# Sheet1.net
KiCad netlist of a schematic drawn in Altium Designer
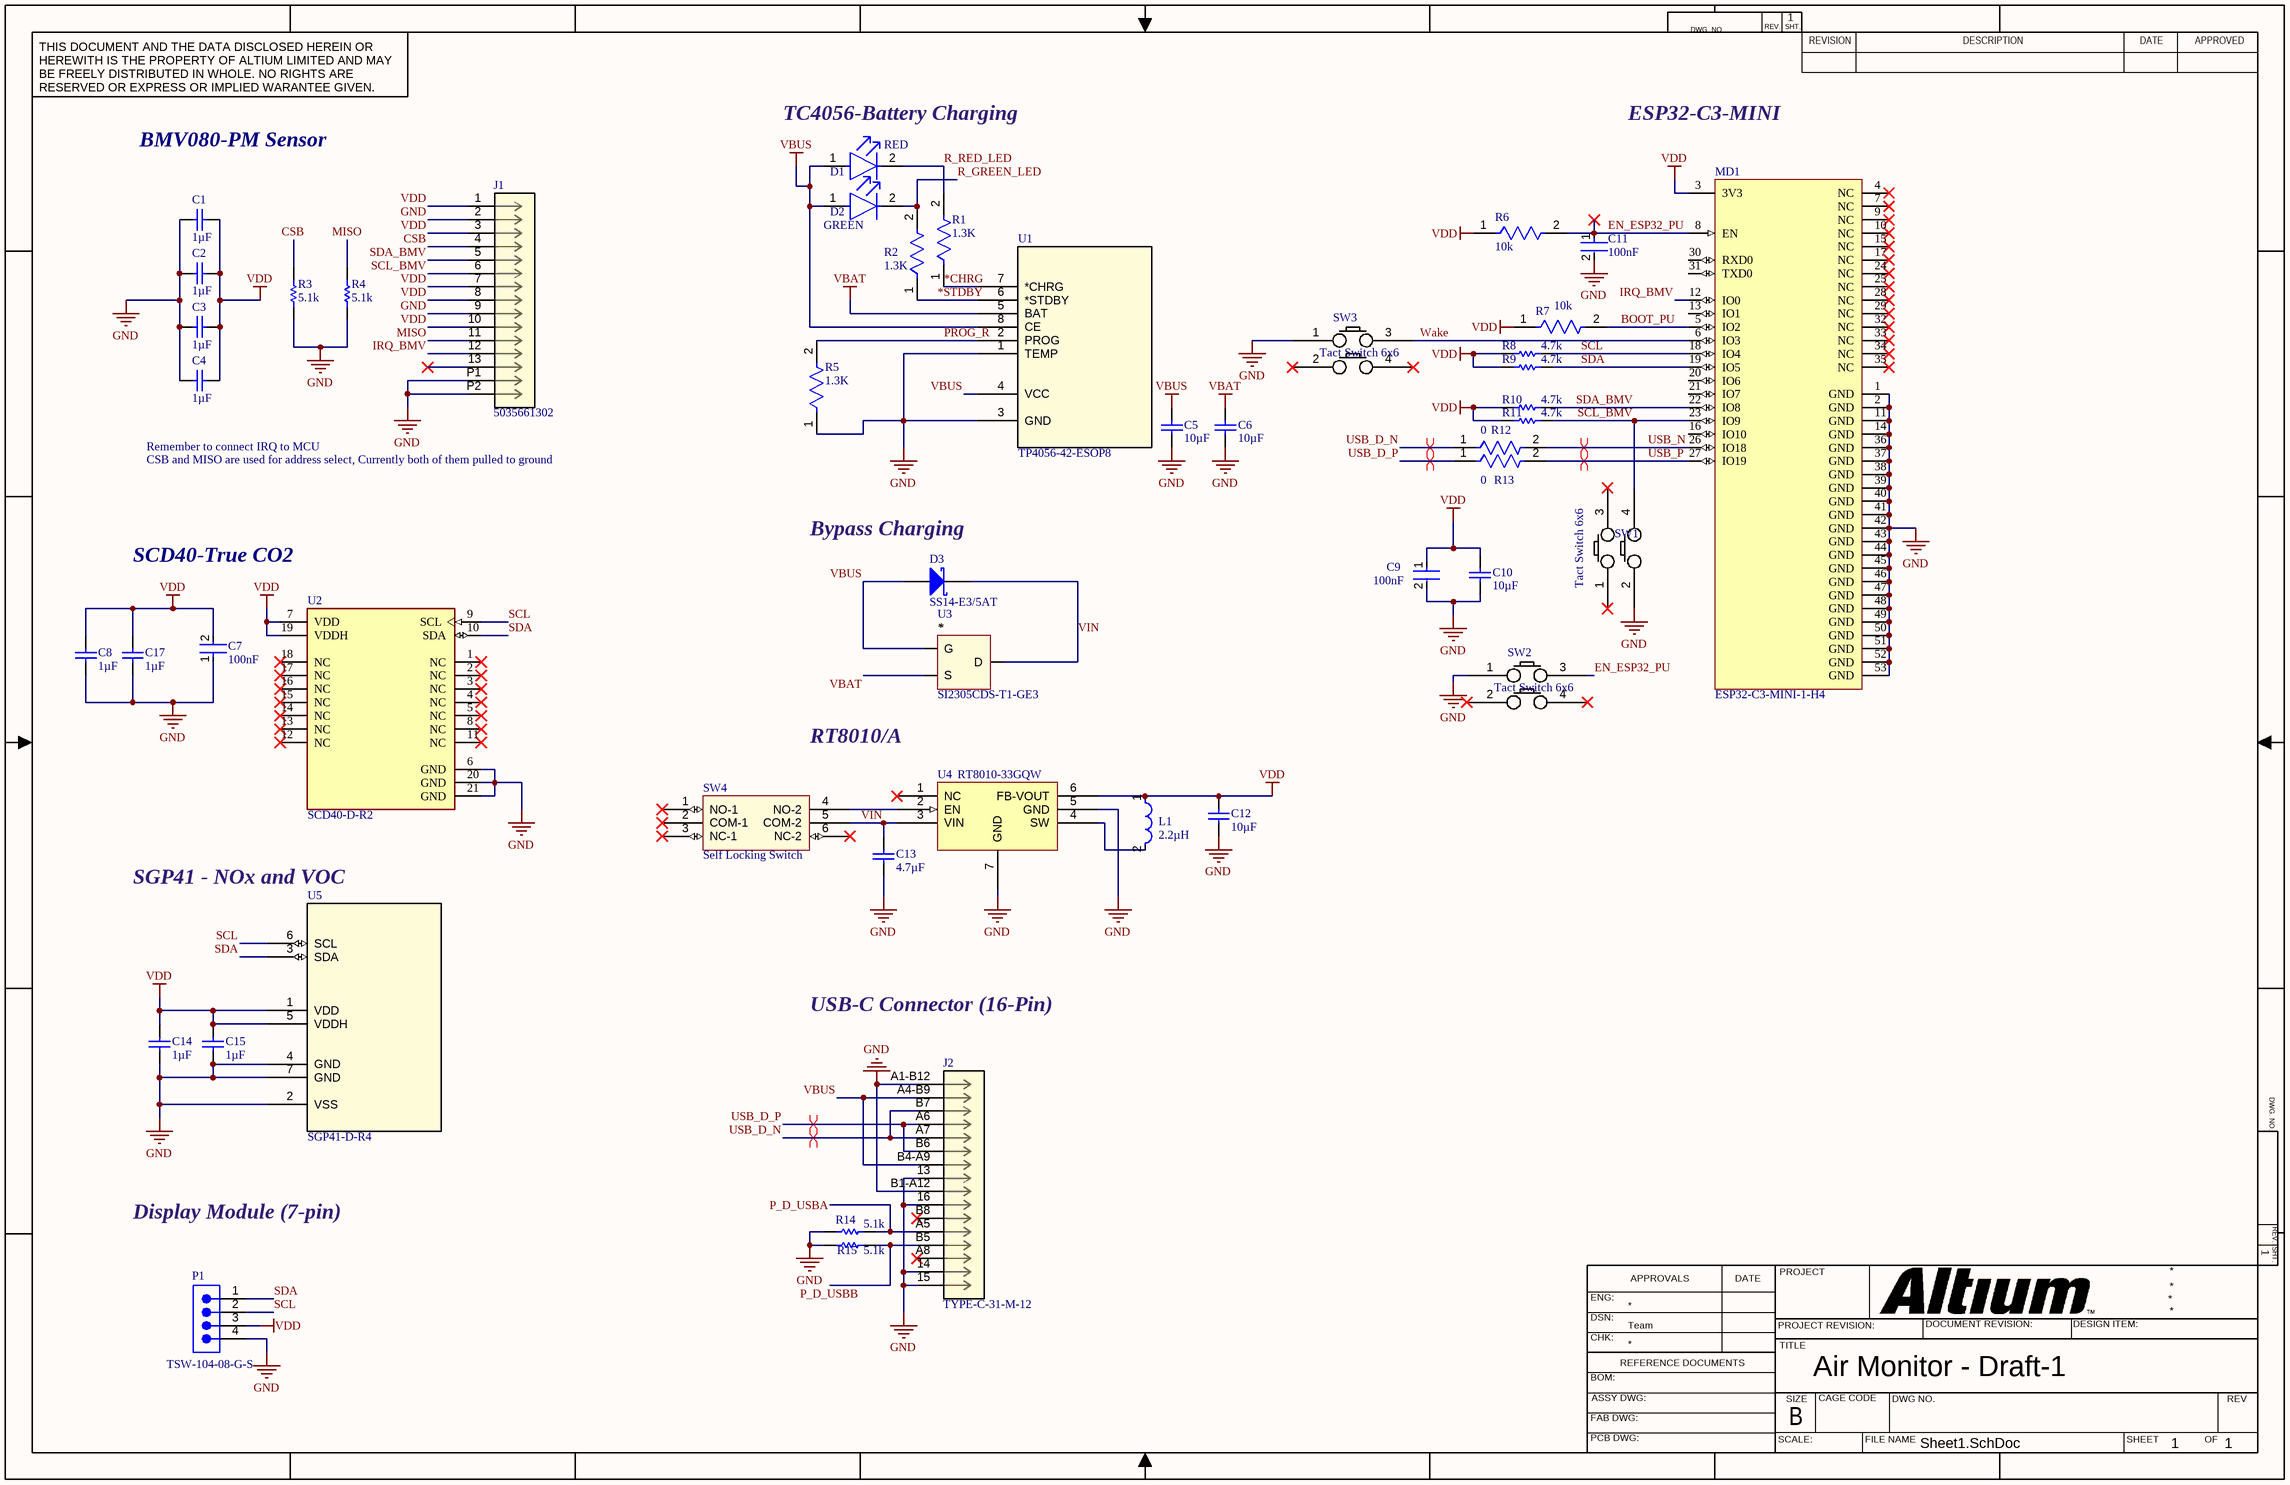
[diagram p0: Sheet1.SchDoc]

(export (version "E")
  (design (tool "Eeschema 10.0.6"))
  (components
    (comp (ref "C1")
      (value "1µF")
      (footprint "CAPC1608X90X35LL15T15")
      (description "16V 1uF X7R ±10% 0603 Multilayer Ceramic Capacitors MLCC - SMD/SMT ROHS")
      (fields (field (name "TOLERANCE") "10%") (field (name "VOLTAGE") "16V"))
      (libsource (lib "Shubhang Kulkarni") (part "CAP"))
    )
    (comp (ref "C2")
      (value "1µF")
      (footprint "CAPC1608X90X35LL15T15")
      (description "16V 1uF X7R ±10% 0603 Multilayer Ceramic Capacitors MLCC - SMD/SMT ROHS")
      (fields (field (name "TOLERANCE") "10%") (field (name "VOLTAGE") "16V"))
      (libsource (lib "Shubhang Kulkarni") (part "CAP"))
    )
    (comp (ref "C3")
      (value "1µF")
      (footprint "CAPC1608X90X35LL15T15")
      (description "16V 1uF X7R ±10% 0603 Multilayer Ceramic Capacitors MLCC - SMD/SMT ROHS")
      (fields (field (name "TOLERANCE") "10%") (field (name "VOLTAGE") "16V"))
      (libsource (lib "Shubhang Kulkarni") (part "CAP"))
    )
    (comp (ref "C4")
      (value "1µF")
      (footprint "CAPC1608X90X35LL15T15")
      (description "16V 1uF X7R ±10% 0603 Multilayer Ceramic Capacitors MLCC - SMD/SMT ROHS")
      (fields (field (name "TOLERANCE") "10%") (field (name "VOLTAGE") "16V"))
      (libsource (lib "Shubhang Kulkarni") (part "CAP"))
    )
    (comp (ref "C5")
      (value "10µF")
      (footprint "CAPC2013X140X45LL15T25")
      (description "Multilayer Ceramic Capacitor, 10 uF, 10 V, ± 10%, X7R, 0805 [2012 Metric]")
      (fields (field (name "TOLERANCE") "10%") (field (name "VOLTAGE") "10V"))
      (libsource (lib "Shubhang Kulkarni") (part "CAP"))
    )
    (comp (ref "C6")
      (value "10µF")
      (footprint "CAPC2013X140X45LL15T25")
      (description "Multilayer Ceramic Capacitor, 10 uF, 10 V, ± 10%, X7R, 0805 [2012 Metric]")
      (fields (field (name "TOLERANCE") "10%") (field (name "VOLTAGE") "10V"))
      (libsource (lib "Shubhang Kulkarni") (part "CAP"))
    )
    (comp (ref "C7")
      (value "100nF")
      (footprint "FP-CC0603-DA-IPC_B")
      (description "Multilayer Ceramic Capacitor, CC Series, 0.1 - F, - 10%, X7R, 50 V, 0603 [1608 Metric]")
      (fields (field (name "VOLTAGE") "50V") (field (name "TOLERANCE") "10%"))
      (libsource (lib "Shubhang Kulkarni") (part "11868f565c42a9108669ba33697ecf6"))
    )
    (comp (ref "C8")
      (value "1µF")
      (footprint "CAPC1608X90X35LL15T15")
      (description "16V 1uF X7R ±10% 0603 Multilayer Ceramic Capacitors MLCC - SMD/SMT ROHS")
      (fields (field (name "TOLERANCE") "10%") (field (name "VOLTAGE") "16V"))
      (libsource (lib "Shubhang Kulkarni") (part "CAP"))
    )
    (comp (ref "C9")
      (value "100nF")
      (footprint "FP-CC0603-DA-IPC_B")
      (description "Multilayer Ceramic Capacitor, CC Series, 0.1 - F, - 10%, X7R, 50 V, 0603 [1608 Metric]")
      (fields (field (name "VOLTAGE") "50V") (field (name "TOLERANCE") "10%"))
      (libsource (lib "Shubhang Kulkarni") (part "11868f565c42a9108669ba33697ecf6"))
    )
    (comp (ref "C10")
      (value "10µF")
      (footprint "CAPC2013X140X45LL15T25")
      (description "Multilayer Ceramic Capacitor, 10 uF, 10 V, ± 10%, X7R, 0805 [2012 Metric]")
      (fields (field (name "TOLERANCE") "10%") (field (name "VOLTAGE") "10V"))
      (libsource (lib "Shubhang Kulkarni") (part "CAP"))
    )
    (comp (ref "C11")
      (value "100nF")
      (footprint "FP-CC0603-DA-IPC_B")
      (description "Multilayer Ceramic Capacitor, CC Series, 0.1 - F, - 10%, X7R, 50 V, 0603 [1608 Metric]")
      (fields (field (name "VOLTAGE") "50V") (field (name "TOLERANCE") "10%"))
      (libsource (lib "Shubhang Kulkarni") (part "11868f565c42a9108669ba33697ecf6"))
    )
    (comp (ref "C12")
      (value "10µF")
      (footprint "CAPC2013X140X45LL15T25")
      (description "Multilayer Ceramic Capacitor, 10 uF, 10 V, ± 10%, X7R, 0805 [2012 Metric]")
      (fields (field (name "TOLERANCE") "10%") (field (name "VOLTAGE") "10V"))
      (libsource (lib "Shubhang Kulkarni") (part "CAP"))
    )
    (comp (ref "C13")
      (value "4.7µF")
      (footprint "CAPC2013X140X50LL20T25")
      (description "0805 Standard 4.7UF Ceramic Multilayer Cap, 25V DC, +85C, X5R Dielectric, +/-10% SMD")
      (fields (field (name "VOLTAGE") "25V") (field (name "TOLERANCE") "10%"))
      (libsource (lib "Shubhang Kulkarni") (part "CAP"))
    )
    (comp (ref "C14")
      (value "1µF")
      (footprint "CAPC1608X90X35LL15T15")
      (description "16V 1uF X7R ±10% 0603 Multilayer Ceramic Capacitors MLCC - SMD/SMT ROHS")
      (fields (field (name "TOLERANCE") "10%") (field (name "VOLTAGE") "16V"))
      (libsource (lib "Shubhang Kulkarni") (part "CAP"))
    )
    (comp (ref "C15")
      (value "1µF")
      (footprint "CAPC1608X90X35LL15T15")
      (description "16V 1uF X7R ±10% 0603 Multilayer Ceramic Capacitors MLCC - SMD/SMT ROHS")
      (fields (field (name "TOLERANCE") "10%") (field (name "VOLTAGE") "16V"))
      (libsource (lib "Shubhang Kulkarni") (part "CAP"))
    )
    (comp (ref "C17")
      (value "1µF")
      (footprint "CAPC1608X90X35LL15T15")
      (description "16V 1uF X7R ±10% 0603 Multilayer Ceramic Capacitors MLCC - SMD/SMT ROHS")
      (fields (field (name "TOLERANCE") "10%") (field (name "VOLTAGE") "16V"))
      (libsource (lib "Shubhang Kulkarni") (part "CAP"))
    )
    (comp (ref "D1")
      (value "RED")
      (footprint "FP-SM0805YCL-MFG")
      (description "LED YELLOW CLEAR 0805 SMD")
      (libsource (lib "Altium Content Vault") (part "ab1c01a81903e929fc6c44469aada92"))
    )
    (comp (ref "D2")
      (value "GREEN")
      (footprint "FP-SM0805YCL-MFG")
      (description "LED YELLOW CLEAR 0805 SMD")
      (libsource (lib "Altium Content Vault") (part "ab1c01a81903e929fc6c44469aada92"))
    )
    (comp (ref "D3")
      (value "SS14-E3/5AT")
      (footprint "VISH-DO-214AC-2_V")
      (description "Rectifier Diode, Schottky, 1 Phase, 1 Element, 1A, 40V V(RRM), Silicon, DO-214AC")
      (libsource (lib "Shubhang Kulkarni") (part "VISH-DSKY_A1K2-2"))
    )
    (comp (ref "J1")
      (value "5035661302")
      (footprint "CON_5035661302_MOL")
      (fields (field (name "COPYRIGHT") "Copyright (C) 2026 Ultra Librarian. All rights reserved."))
      (libsource (lib "Shubhang Kulkarni") (part "5035661302"))
    )
    (comp (ref "J2")
      (value "TYPE-C-31-M-12")
      (footprint "CONN12_C-31-M-12_HRO")
      (description "Description")
      (fields (field (name "COPYRIGHT") "Copyright (C) 2025 Ultra Librarian. All rights reserved."))
      (libsource (lib "Shubhang Kulkarni") (part "TYPE-C-31-M-12"))
    )
    (comp (ref "L1")
      (value "2.2µH")
      (footprint "FP-NR6028-MFG")
      (description "Inductor Power Shielded Wirewound 2.2uH 30% 100KHz Ferrite 3.7A 0.026Ohm DCR 2424 T/R")
      (fields (field (name "TOLERANCE") "30%") (field (name "Comment") "NRS6028T2R2NMGJ"))
      (libsource (lib "Shubhang Kulkarni") (part "725321dda6339637d4d059423bc1c3c"))
    )
    (comp (ref "MD1")
      (value "ESP32-C3-MINI-1-H4")
      (footprint "FP-ESP32-C3-MINI-1-H4-MFG")
      (description "-96dBm 20.5dBm PCBAntenna 2.4GHz SMD, 13.2x16.6mm WiFi Modules ROHS")
      (libsource (lib "Shubhang Kulkarni") (part "ESP32-C3-MINI-1-H4"))
    )
    (comp (ref "P1")
      (value "TSW-104-08-G-S")
      (footprint "SMTC-TSW-104-08-X-S")
      (description "0.025\" SQ Post Header, Through-hole, Vertical, -55 to 125 degC, 2.54 mm Pitch, 4-Pin, Male, RoHS")
      (fields (field (name "MANUFACTURER") "Samtec"))
      (libsource (lib "Altium Content Vault") (part "SMTC-TSW-104-08-X-S"))
    )
    (comp (ref "R1")
      (value "1.3K")
      (footprint "FP-AC0603-IPC_B")
      (description "RES 1.3KΩ 1.00% 0.1W 0603")
      (fields (field (name "TOLERANCE") "1%"))
      (libsource (lib "Altium Content Vault") (part "1029c3af85768c4190bb7ad29bc67b5"))
    )
    (comp (ref "R2")
      (value "1.3K")
      (footprint "FP-AC0603-IPC_B")
      (description "RES 1.3KΩ 1.00% 0.1W 0603")
      (fields (field (name "TOLERANCE") "1%"))
      (libsource (lib "Altium Content Vault") (part "1029c3af85768c4190bb7ad29bc67b5"))
    )
    (comp (ref "R3")
      (value "5.1k")
      (footprint "RESC1608X55X25ML10T15")
      (description "Res Thick Film 0603 5.1K Ohm 1% 0.1W(1/10W) ±100ppm/C Pad SMD T/R")
      (fields (field (name "TOLERANCE") "1%") (field (name "Comment") "RC0603FR-075K1L"))
      (libsource (lib "Shubhang Kulkarni") (part "RES"))
    )
    (comp (ref "R4")
      (value "5.1k")
      (footprint "RESC1608X55X25ML10T15")
      (description "Res Thick Film 0603 5.1K Ohm 1% 0.1W(1/10W) ±100ppm/C Pad SMD T/R")
      (fields (field (name "TOLERANCE") "1%") (field (name "Comment") "RC0603FR-075K1L"))
      (libsource (lib "Shubhang Kulkarni") (part "RES"))
    )
    (comp (ref "R5")
      (value "1.3K")
      (footprint "FP-AC0603-IPC_B")
      (description "RES 1.3KΩ 1.00% 0.1W 0603")
      (fields (field (name "TOLERANCE") "1%"))
      (libsource (lib "Altium Content Vault") (part "1029c3af85768c4190bb7ad29bc67b5"))
    )
    (comp (ref "R6")
      (value "10k")
      (footprint "FP-RC0603-0_55-IPC_C")
      (description "100mW Thick Film Resistors ±100ppm/℃ ±1% 10kΩ 0603 Chip Resistor - Surface Mount ROHS")
      (fields (field (name "TOLERANCE") "1%") (field (name "Comment") "RC0603FR-0710KL"))
      (libsource (lib "Shubhang Kulkarni") (part "1029c3af85768c4190bb7ad29bc67b5"))
    )
    (comp (ref "R7")
      (value "10k")
      (footprint "FP-RC0603-0_55-IPC_C")
      (description "100mW Thick Film Resistors ±100ppm/℃ ±1% 10kΩ 0603 Chip Resistor - Surface Mount ROHS")
      (fields (field (name "TOLERANCE") "1%") (field (name "Comment") "RC0603FR-0710KL"))
      (libsource (lib "Shubhang Kulkarni") (part "1029c3af85768c4190bb7ad29bc67b5"))
    )
    (comp (ref "R8")
      (value "4.7k")
      (footprint "RESC1608X55X25LL10T15")
      (description "Res Thick Film 1.6 x 0.8 mm 4.7K Ohm 1% 0.1W(1/10W) 100ppm/ C Molded SMD Paper T/R")
      (fields (field (name "TOLERANCE") "1%") (field (name "Comment") "RC0603FR-074K7L"))
      (libsource (lib "Shubhang Kulkarni") (part "RES-2"))
    )
    (comp (ref "R9")
      (value "4.7k")
      (footprint "RESC1608X55X25LL10T15")
      (description "Res Thick Film 1.6 x 0.8 mm 4.7K Ohm 1% 0.1W(1/10W) 100ppm/ C Molded SMD Paper T/R")
      (fields (field (name "TOLERANCE") "1%") (field (name "Comment") "RC0603FR-074K7L"))
      (libsource (lib "Shubhang Kulkarni") (part "RES-2"))
    )
    (comp (ref "R10")
      (value "4.7k")
      (footprint "RESC1608X55X25LL10T15")
      (description "Res Thick Film 1.6 x 0.8 mm 4.7K Ohm 1% 0.1W(1/10W) 100ppm/ C Molded SMD Paper T/R")
      (fields (field (name "TOLERANCE") "1%") (field (name "Comment") "RC0603FR-074K7L"))
      (libsource (lib "Shubhang Kulkarni") (part "RES-2"))
    )
    (comp (ref "R11")
      (value "4.7k")
      (footprint "RESC1608X55X25LL10T15")
      (description "Res Thick Film 1.6 x 0.8 mm 4.7K Ohm 1% 0.1W(1/10W) 100ppm/ C Molded SMD Paper T/R")
      (fields (field (name "TOLERANCE") "1%") (field (name "Comment") "RC0603FR-074K7L"))
      (libsource (lib "Shubhang Kulkarni") (part "RES-2"))
    )
    (comp (ref "R12")
      (value "0")
      (footprint "FP-RC0603-MFG")
      (description "Zero Ohm Resistor, Jumper, 0603 [1608 Metric], Thick Film, 100 mW, 1 A, Surface Mount")
      (fields (field (name "TOLERANCE") "1%") (field (name "Comment") "RC0603FR-070RL"))
      (libsource (lib "Shubhang Kulkarni") (part "1029c3af85768c4190bb7ad29bc67b5"))
    )
    (comp (ref "R13")
      (value "0")
      (footprint "FP-RC0603-MFG")
      (description "Zero Ohm Resistor, Jumper, 0603 [1608 Metric], Thick Film, 100 mW, 1 A, Surface Mount")
      (fields (field (name "TOLERANCE") "1%") (field (name "Comment") "RC0603FR-070RL"))
      (libsource (lib "Shubhang Kulkarni") (part "1029c3af85768c4190bb7ad29bc67b5"))
    )
    (comp (ref "R14")
      (value "5.1k")
      (footprint "RESC1608X55X25ML10T15")
      (description "Res Thick Film 0603 5.1K Ohm 1% 0.1W(1/10W) ±100ppm/C Pad SMD T/R")
      (fields (field (name "TOLERANCE") "1%") (field (name "Comment") "RC0603FR-075K1L"))
      (libsource (lib "Shubhang Kulkarni") (part "RES"))
    )
    (comp (ref "R15")
      (value "5.1k")
      (footprint "RESC1608X55X25ML10T15")
      (description "Res Thick Film 0603 5.1K Ohm 1% 0.1W(1/10W) ±100ppm/C Pad SMD T/R")
      (fields (field (name "TOLERANCE") "1%") (field (name "Comment") "RC0603FR-075K1L"))
      (libsource (lib "Shubhang Kulkarni") (part "RES"))
    )
    (comp (ref "SW1")
      (value "Tact Switch 6x6")
      (footprint "Tact Switch 6x6-Footprint-1")
      (description "Tact switch- 6x6mm")
      (libsource (lib "Shubhang Kulkarni") (part "Tact Switch"))
    )
    (comp (ref "SW2")
      (value "Tact Switch 6x6")
      (footprint "Tact Switch 6x6-Footprint-1")
      (description "Tact switch- 6x6mm")
      (libsource (lib "Shubhang Kulkarni") (part "Tact Switch"))
    )
    (comp (ref "SW3")
      (value "Tact Switch 6x6")
      (footprint "Tact Switch 6x6-Footprint-1")
      (description "Tact switch- 6x6mm")
      (libsource (lib "Shubhang Kulkarni") (part "Tact Switch"))
    )
    (comp (ref "SW4")
      (value "Self Locking Switch")
      (footprint "Self Locking Switch-Footprint-1")
      (description "A self locking-latch like switch.")
      (libsource (lib "Shubhang Kulkarni") (part "KFC-5.8C"))
    )
    (comp (ref "U1")
      (value "TP4056-42-ESOP8")
      (footprint "TP4056-42-ESOP8_TPW")
      (description "Description")
      (fields (field (name "COPYRIGHT") "Copyright (C) 2026 Ultra Librarian. All rights reserved."))
      (libsource (lib "Shubhang Kulkarni") (part "TP4056-42-ESOP8"))
    )
    (comp (ref "U2")
      (value "SCD40-D-R2")
      (footprint "FP-SCD40-D-R2-MFG")
      (description "Air Quality Sensor CO2 Sensor 2.5V/3.3V/5V 20-Pin SMD EP T/R")
      (libsource (lib "Shubhang Kulkarni") (part "860b1291be8b6ca23305e01f328347a"))
    )
    (comp (ref "U3")
      (value "SI2305CDS-T1-GE3")
      (footprint "TO-236_VIS")
      (description "P-CHANNEL 8-V (D-S) MOSFET")
      (fields (field (name "COPYRIGHT") "Copyright (C) 2025 Ultra Librarian. All rights reserved."))
      (libsource (lib "Shubhang Kulkarni") (part "SI2305CDS-T1-GE3"))
    )
    (comp (ref "U4")
      (value "RT8010-33GQW")
      (footprint "RT8010-GQW")
      (description "Switching Regulator, Voltage-mode, 1A, 1800kHz Switching Freq-Max, PDSO6")
      (libsource (lib "Shubhang Kulkarni") (part "RT8010"))
    )
    (comp (ref "U5")
      (value "SGP41-D-R4")
      (footprint "DFN_SGP41-D-R4_SEN")
      (description "NOx and VOC Sensor with a Secondary Humidity and Temperature Output")
      (fields (field (name "COPYRIGHT") "Copyright (C) 2026 Ultra Librarian. All rights reserved."))
      (libsource (lib "Shubhang Kulkarni") (part "SGP41-D-R4"))
    )
  )
  (nets
    (net (code "1") (name "/*CHRG") (class "Default")
      (node (ref "R1") (pin "1") (pinfunction "1_1") (pintype "passive"))
      (node (ref "U1") (pin "7") (pinfunction "*CHRG_7") (pintype "passive"))
    )
    (net (code "2") (name "/*STDBY") (class "Default")
      (node (ref "R2") (pin "1") (pinfunction "1_1") (pintype "passive"))
      (node (ref "U1") (pin "6") (pinfunction "*STDBY_6") (pintype "passive"))
    )
    (net (code "3") (name "/BOOT_PU") (class "Default")
      (node (ref "MD1") (pin "5") (pinfunction "IO2_5") (pintype "bidirectional"))
      (node (ref "R7") (pin "2") (pinfunction "2_2") (pintype "passive"))
    )
    (net (code "4") (name "/CSB") (class "Default")
      (node (ref "J1") (pin "4") (pinfunction "4_4") (pintype "passive"))
      (node (ref "R3") (pin "2") (pinfunction "2_2") (pintype "passive"))
    )
    (net (code "5") (name "/EN_ESP32_PU") (class "Default")
      (node (ref "C11") (pin "1") (pinfunction "1_1") (pintype "passive"))
      (node (ref "MD1") (pin "8") (pinfunction "EN_8") (pintype "input"))
      (node (ref "R6") (pin "2") (pinfunction "2_2") (pintype "passive"))
      (node (ref "SW2") (pin "3") (pinfunction "B_3") (pintype "passive"))
    )
    (net (code "6") (name "/IRQ_BMV") (class "Default")
      (node (ref "J1") (pin "12") (pinfunction "12_12") (pintype "passive"))
      (node (ref "MD1") (pin "12") (pinfunction "IO0_12") (pintype "bidirectional"))
    )
    (net (code "7") (name "/MISO") (class "Default")
      (node (ref "J1") (pin "11") (pinfunction "11_11") (pintype "passive"))
      (node (ref "R4") (pin "2") (pinfunction "2_2") (pintype "passive"))
    )
    (net (code "8") (name "/PROG_R") (class "Default")
      (node (ref "R5") (pin "2") (pinfunction "2_2") (pintype "passive"))
      (node (ref "U1") (pin "2") (pinfunction "PROG_2") (pintype "passive"))
    )
    (net (code "9") (name "/P_D_USBA") (class "Default")
      (node (ref "J2") (pin "A5") (pinfunction "A5_A5") (pintype "passive"))
      (node (ref "R14") (pin "2") (pinfunction "2_2") (pintype "passive"))
    )
    (net (code "10") (name "/P_D_USBB") (class "Default")
      (node (ref "J2") (pin "B5") (pinfunction "B5_B5") (pintype "passive"))
      (node (ref "R15") (pin "2") (pinfunction "2_2") (pintype "passive"))
    )
    (net (code "11") (name "/R_GREEN_LED") (class "Default")
      (node (ref "D2") (pin "2") (pinfunction "C_2") (pintype "passive"))
      (node (ref "R2") (pin "2") (pinfunction "2_2") (pintype "passive"))
    )
    (net (code "12") (name "/R_RED_LED") (class "Default")
      (node (ref "D1") (pin "2") (pinfunction "C_2") (pintype "passive"))
      (node (ref "R1") (pin "2") (pinfunction "2_2") (pintype "passive"))
    )
    (net (code "13") (name "/SCL") (class "Default")
      (node (ref "MD1") (pin "18") (pinfunction "IO4_18") (pintype "bidirectional"))
      (node (ref "P1") (pin "2") (pinfunction "2_2") (pintype "passive"))
      (node (ref "R8") (pin "2") (pinfunction "2_2") (pintype "passive"))
      (node (ref "U2") (pin "9") (pinfunction "SCL_9") (pintype "input"))
      (node (ref "U5") (pin "6") (pinfunction "SCL_6") (pintype "bidirectional"))
    )
    (net (code "14") (name "/SCL_BMV") (class "Default")
      (node (ref "J1") (pin "6") (pinfunction "6_6") (pintype "passive"))
      (node (ref "MD1") (pin "23") (pinfunction "IO9_23") (pintype "bidirectional"))
      (node (ref "R11") (pin "2") (pinfunction "2_2") (pintype "passive"))
      (node (ref "SW1") (pin "4") (pinfunction "B_4") (pintype "passive"))
    )
    (net (code "15") (name "/SDA") (class "Default")
      (node (ref "MD1") (pin "19") (pinfunction "IO5_19") (pintype "bidirectional"))
      (node (ref "P1") (pin "1") (pinfunction "1_1") (pintype "passive"))
      (node (ref "R9") (pin "2") (pinfunction "2_2") (pintype "passive"))
      (node (ref "U2") (pin "10") (pinfunction "SDA_10") (pintype "bidirectional"))
      (node (ref "U5") (pin "3") (pinfunction "SDA_3") (pintype "bidirectional"))
    )
    (net (code "16") (name "/SDA_BMV") (class "Default")
      (node (ref "J1") (pin "5") (pinfunction "5_5") (pintype "passive"))
      (node (ref "MD1") (pin "22") (pinfunction "IO8_22") (pintype "bidirectional"))
      (node (ref "R10") (pin "2") (pinfunction "2_2") (pintype "passive"))
    )
    (net (code "17") (name "/USB_D_N") (class "Default")
      (node (ref "J2") (pin "A7") (pinfunction "A7_A7") (pintype "passive"))
      (node (ref "J2") (pin "B7") (pinfunction "B7_B7") (pintype "passive"))
      (node (ref "R12") (pin "1") (pinfunction "1_1") (pintype "passive"))
    )
    (net (code "18") (name "/USB_D_P") (class "Default")
      (node (ref "J2") (pin "A6") (pinfunction "A6_A6") (pintype "passive"))
      (node (ref "J2") (pin "B6") (pinfunction "B6_B6") (pintype "passive"))
      (node (ref "R13") (pin "1") (pinfunction "1_1") (pintype "passive"))
    )
    (net (code "19") (name "/USB_N") (class "Default")
      (node (ref "MD1") (pin "26") (pinfunction "IO18_26") (pintype "bidirectional"))
      (node (ref "R12") (pin "2") (pinfunction "2_2") (pintype "passive"))
    )
    (net (code "20") (name "/USB_P") (class "Default")
      (node (ref "MD1") (pin "27") (pinfunction "IO19_27") (pintype "bidirectional"))
      (node (ref "R13") (pin "2") (pinfunction "2_2") (pintype "passive"))
    )
    (net (code "21") (name "/VIN") (class "Default")
      (node (ref "C13") (pin "2") (pinfunction "2_2") (pintype "passive"))
      (node (ref "D3") (pin "2") (pinfunction "K_2") (pintype "passive"))
      (node (ref "SW4") (pin "5") (pinfunction "COM-2_5") (pintype "power_in"))
      (node (ref "U3") (pin "2") (pinfunction "D_2") (pintype "passive"))
      (node (ref "U4") (pin "3") (pinfunction "VIN_3") (pintype "power_in"))
    )
    (net (code "22") (name "/Wake") (class "Default")
      (node (ref "MD1") (pin "6") (pinfunction "IO3_6") (pintype "bidirectional"))
      (node (ref "SW3") (pin "3") (pinfunction "B_3") (pintype "passive"))
    )
    (net (code "23") (name "GND") (class "Default")
      (node (ref "C1") (pin "1") (pinfunction "1_1") (pintype "passive"))
      (node (ref "C10") (pin "1") (pinfunction "1_1") (pintype "passive"))
      (node (ref "C11") (pin "2") (pinfunction "2_2") (pintype "passive"))
      (node (ref "C12") (pin "1") (pinfunction "1_1") (pintype "passive"))
      (node (ref "C13") (pin "1") (pinfunction "1_1") (pintype "passive"))
      (node (ref "C14") (pin "1") (pinfunction "1_1") (pintype "passive"))
      (node (ref "C15") (pin "1") (pinfunction "1_1") (pintype "passive"))
      (node (ref "C17") (pin "1") (pinfunction "1_1") (pintype "passive"))
      (node (ref "C2") (pin "1") (pinfunction "1_1") (pintype "passive"))
      (node (ref "C3") (pin "1") (pinfunction "1_1") (pintype "passive"))
      (node (ref "C4") (pin "1") (pinfunction "1_1") (pintype "passive"))
      (node (ref "C5") (pin "1") (pinfunction "1_1") (pintype "passive"))
      (node (ref "C6") (pin "1") (pinfunction "1_1") (pintype "passive"))
      (node (ref "C7") (pin "1") (pinfunction "1_1") (pintype "passive"))
      (node (ref "C8") (pin "1") (pinfunction "1_1") (pintype "passive"))
      (node (ref "C9") (pin "2") (pinfunction "2_2") (pintype "passive"))
      (node (ref "J1") (pin "2") (pinfunction "2_2") (pintype "passive"))
      (node (ref "J1") (pin "9") (pinfunction "9_9") (pintype "passive"))
      (node (ref "J1") (pin "P1") (pinfunction "P1_P1") (pintype "passive"))
      (node (ref "J1") (pin "P2") (pinfunction "P2_P2") (pintype "passive"))
      (node (ref "J2") (pin "13") (pinfunction "13_13") (pintype "passive"))
      (node (ref "J2") (pin "14") (pinfunction "14_14") (pintype "passive"))
      (node (ref "J2") (pin "15") (pinfunction "15_15") (pintype "passive"))
      (node (ref "J2") (pin "16") (pinfunction "16_16") (pintype "passive"))
      (node (ref "J2") (pin "A1-B12") (pinfunction "A1-B12_A1-B12") (pintype "passive"))
      (node (ref "J2") (pin "B1-A12") (pinfunction "B1-A12_B1-A12") (pintype "passive"))
      (node (ref "MD1") (pin "1") (pinfunction "GND_1") (pintype "power_in"))
      (node (ref "MD1") (pin "11") (pinfunction "GND_11") (pintype "power_in"))
      (node (ref "MD1") (pin "14") (pinfunction "GND_14") (pintype "power_in"))
      (node (ref "MD1") (pin "2") (pinfunction "GND_2") (pintype "power_in"))
      (node (ref "MD1") (pin "36") (pinfunction "GND_36") (pintype "power_in"))
      (node (ref "MD1") (pin "37") (pinfunction "GND_37") (pintype "power_in"))
      (node (ref "MD1") (pin "38") (pinfunction "GND_38") (pintype "power_in"))
      (node (ref "MD1") (pin "39") (pinfunction "GND_39") (pintype "power_in"))
      (node (ref "MD1") (pin "40") (pinfunction "GND_40") (pintype "power_in"))
      (node (ref "MD1") (pin "41") (pinfunction "GND_41") (pintype "power_in"))
      (node (ref "MD1") (pin "42") (pinfunction "GND_42") (pintype "power_in"))
      (node (ref "MD1") (pin "43") (pinfunction "GND_43") (pintype "power_in"))
      (node (ref "MD1") (pin "44") (pinfunction "GND_44") (pintype "power_in"))
      (node (ref "MD1") (pin "45") (pinfunction "GND_45") (pintype "power_in"))
      (node (ref "MD1") (pin "46") (pinfunction "GND_46") (pintype "power_in"))
      (node (ref "MD1") (pin "47") (pinfunction "GND_47") (pintype "power_in"))
      (node (ref "MD1") (pin "48") (pinfunction "GND_48") (pintype "power_in"))
      (node (ref "MD1") (pin "49") (pinfunction "GND_49") (pintype "power_in"))
      (node (ref "MD1") (pin "50") (pinfunction "GND_50") (pintype "power_in"))
      (node (ref "MD1") (pin "51") (pinfunction "GND_51") (pintype "power_in"))
      (node (ref "MD1") (pin "52") (pinfunction "GND_52") (pintype "power_in"))
      (node (ref "MD1") (pin "53") (pinfunction "GND_53") (pintype "power_in"))
      (node (ref "P1") (pin "4") (pinfunction "4_4") (pintype "passive"))
      (node (ref "R14") (pin "1") (pinfunction "1_1") (pintype "passive"))
      (node (ref "R15") (pin "1") (pinfunction "1_1") (pintype "passive"))
      (node (ref "R3") (pin "1") (pinfunction "1_1") (pintype "passive"))
      (node (ref "R4") (pin "1") (pinfunction "1_1") (pintype "passive"))
      (node (ref "R5") (pin "1") (pinfunction "1_1") (pintype "passive"))
      (node (ref "SW1") (pin "2") (pinfunction "A_2") (pintype "passive"))
      (node (ref "SW2") (pin "1") (pinfunction "A_1") (pintype "passive"))
      (node (ref "SW3") (pin "1") (pinfunction "A_1") (pintype "passive"))
      (node (ref "U1") (pin "1") (pinfunction "TEMP_1") (pintype "passive"))
      (node (ref "U1") (pin "3") (pinfunction "GND_3") (pintype "power_in"))
      (node (ref "U2") (pin "20") (pinfunction "GND_20") (pintype "power_in"))
      (node (ref "U2") (pin "21") (pinfunction "GND_21") (pintype "power_in"))
      (node (ref "U2") (pin "6") (pinfunction "GND_6") (pintype "power_in"))
      (node (ref "U4") (pin "5") (pinfunction "GND_5") (pintype "power_in"))
      (node (ref "U4") (pin "7") (pinfunction "GND_7") (pintype "power_in"))
      (node (ref "U5") (pin "2") (pinfunction "VSS_2") (pintype "power_in"))
      (node (ref "U5") (pin "4") (pinfunction "GND_4") (pintype "power_in"))
      (node (ref "U5") (pin "7") (pinfunction "GND_7") (pintype "power_in"))
    )
    (net (code "24") (name "Net-(SW4-NO-2)") (class "Default")
      (node (ref "SW4") (pin "4") (pinfunction "NO-2_4") (pintype "power_in"))
      (node (ref "U4") (pin "2") (pinfunction "EN_2") (pintype "input"))
    )
    (net (code "25") (name "Net-(U4-SW)") (class "Default")
      (node (ref "L1") (pin "2") (pinfunction "2_2") (pintype "passive"))
      (node (ref "U4") (pin "4") (pinfunction "SW_4") (pintype "power_in"))
    )
    (net (code "26") (name "VBAT") (class "Default")
      (node (ref "C6") (pin "2") (pinfunction "2_2") (pintype "passive"))
      (node (ref "U1") (pin "5") (pinfunction "BAT_5") (pintype "passive"))
      (node (ref "U3") (pin "3") (pinfunction "S_3") (pintype "passive"))
    )
    (net (code "27") (name "VBUS") (class "Default")
      (node (ref "C5") (pin "2") (pinfunction "2_2") (pintype "passive"))
      (node (ref "D1") (pin "1") (pinfunction "A_1") (pintype "passive"))
      (node (ref "D2") (pin "1") (pinfunction "A_1") (pintype "passive"))
      (node (ref "D3") (pin "1") (pinfunction "A_1") (pintype "passive"))
      (node (ref "J2") (pin "A4-B9") (pinfunction "A4-B9_A4-B9") (pintype "passive"))
      (node (ref "J2") (pin "B4-A9") (pinfunction "B4-A9_B4-A9") (pintype "passive"))
      (node (ref "U1") (pin "4") (pinfunction "VCC_4") (pintype "power_in"))
      (node (ref "U1") (pin "8") (pinfunction "CE_8") (pintype "passive"))
      (node (ref "U3") (pin "1") (pinfunction "G_1") (pintype "passive"))
    )
    (net (code "28") (name "VDD") (class "Default")
      (node (ref "C1") (pin "2") (pinfunction "2_2") (pintype "passive"))
      (node (ref "C10") (pin "2") (pinfunction "2_2") (pintype "passive"))
      (node (ref "C12") (pin "2") (pinfunction "2_2") (pintype "passive"))
      (node (ref "C14") (pin "2") (pinfunction "2_2") (pintype "passive"))
      (node (ref "C15") (pin "2") (pinfunction "2_2") (pintype "passive"))
      (node (ref "C17") (pin "2") (pinfunction "2_2") (pintype "passive"))
      (node (ref "C2") (pin "2") (pinfunction "2_2") (pintype "passive"))
      (node (ref "C3") (pin "2") (pinfunction "2_2") (pintype "passive"))
      (node (ref "C4") (pin "2") (pinfunction "2_2") (pintype "passive"))
      (node (ref "C7") (pin "2") (pinfunction "2_2") (pintype "passive"))
      (node (ref "C8") (pin "2") (pinfunction "2_2") (pintype "passive"))
      (node (ref "C9") (pin "1") (pinfunction "1_1") (pintype "passive"))
      (node (ref "J1") (pin "1") (pinfunction "1_1") (pintype "passive"))
      (node (ref "J1") (pin "10") (pinfunction "10_10") (pintype "passive"))
      (node (ref "J1") (pin "3") (pinfunction "3_3") (pintype "passive"))
      (node (ref "J1") (pin "7") (pinfunction "7_7") (pintype "passive"))
      (node (ref "J1") (pin "8") (pinfunction "8_8") (pintype "passive"))
      (node (ref "L1") (pin "1") (pinfunction "1_1") (pintype "passive"))
      (node (ref "MD1") (pin "3") (pinfunction "3V3_3") (pintype "power_in"))
      (node (ref "P1") (pin "3") (pinfunction "3_3") (pintype "passive"))
      (node (ref "R10") (pin "1") (pinfunction "1_1") (pintype "passive"))
      (node (ref "R11") (pin "1") (pinfunction "1_1") (pintype "passive"))
      (node (ref "R6") (pin "1") (pinfunction "1_1") (pintype "passive"))
      (node (ref "R7") (pin "1") (pinfunction "1_1") (pintype "passive"))
      (node (ref "R8") (pin "1") (pinfunction "1_1") (pintype "passive"))
      (node (ref "R9") (pin "1") (pinfunction "1_1") (pintype "passive"))
      (node (ref "U2") (pin "19") (pinfunction "VDDH_19") (pintype "power_in"))
      (node (ref "U2") (pin "7") (pinfunction "VDD_7") (pintype "power_in"))
      (node (ref "U4") (pin "6") (pinfunction "FB-VOUT_6") (pintype "power_in"))
      (node (ref "U5") (pin "1") (pinfunction "VDD_1") (pintype "power_in"))
      (node (ref "U5") (pin "5") (pinfunction "VDDH_5") (pintype "power_in"))
    )
    (net (code "29") (name "unconnected-(J1-Pad13)") (class "Default")
      (node (ref "J1") (pin "13") (pinfunction "13_13") (pintype "passive+no_connect"))
    )
    (net (code "30") (name "unconnected-(J2-PadA8)") (class "Default")
      (node (ref "J2") (pin "A8") (pinfunction "A8_A8") (pintype "passive+no_connect"))
    )
    (net (code "31") (name "unconnected-(J2-PadB8)") (class "Default")
      (node (ref "J2") (pin "B8") (pinfunction "B8_B8") (pintype "passive+no_connect"))
    )
    (net (code "32") (name "unconnected-(MD1-IO1-Pad13)") (class "Default")
      (node (ref "MD1") (pin "13") (pinfunction "IO1_13") (pintype "bidirectional"))
    )
    (net (code "33") (name "unconnected-(MD1-IO6-Pad20)") (class "Default")
      (node (ref "MD1") (pin "20") (pinfunction "IO6_20") (pintype "bidirectional"))
    )
    (net (code "34") (name "unconnected-(MD1-IO7-Pad21)") (class "Default")
      (node (ref "MD1") (pin "21") (pinfunction "IO7_21") (pintype "bidirectional"))
    )
    (net (code "35") (name "unconnected-(MD1-IO10-Pad16)") (class "Default")
      (node (ref "MD1") (pin "16") (pinfunction "IO10_16") (pintype "bidirectional"))
    )
    (net (code "36") (name "unconnected-(MD1-NC-Pad4)") (class "Default")
      (node (ref "MD1") (pin "4") (pinfunction "NC_4") (pintype "passive+no_connect"))
    )
    (net (code "37") (name "unconnected-(MD1-NC-Pad7)") (class "Default")
      (node (ref "MD1") (pin "7") (pinfunction "NC_7") (pintype "passive+no_connect"))
    )
    (net (code "38") (name "unconnected-(MD1-NC-Pad9)") (class "Default")
      (node (ref "MD1") (pin "9") (pinfunction "NC_9") (pintype "passive+no_connect"))
    )
    (net (code "39") (name "unconnected-(MD1-NC-Pad10)") (class "Default")
      (node (ref "MD1") (pin "10") (pinfunction "NC_10") (pintype "passive+no_connect"))
    )
    (net (code "40") (name "unconnected-(MD1-NC-Pad15)") (class "Default")
      (node (ref "MD1") (pin "15") (pinfunction "NC_15") (pintype "passive+no_connect"))
    )
    (net (code "41") (name "unconnected-(MD1-NC-Pad17)") (class "Default")
      (node (ref "MD1") (pin "17") (pinfunction "NC_17") (pintype "passive+no_connect"))
    )
    (net (code "42") (name "unconnected-(MD1-NC-Pad24)") (class "Default")
      (node (ref "MD1") (pin "24") (pinfunction "NC_24") (pintype "passive+no_connect"))
    )
    (net (code "43") (name "unconnected-(MD1-NC-Pad25)") (class "Default")
      (node (ref "MD1") (pin "25") (pinfunction "NC_25") (pintype "passive+no_connect"))
    )
    (net (code "44") (name "unconnected-(MD1-NC-Pad28)") (class "Default")
      (node (ref "MD1") (pin "28") (pinfunction "NC_28") (pintype "passive+no_connect"))
    )
    (net (code "45") (name "unconnected-(MD1-NC-Pad29)") (class "Default")
      (node (ref "MD1") (pin "29") (pinfunction "NC_29") (pintype "passive+no_connect"))
    )
    (net (code "46") (name "unconnected-(MD1-NC-Pad32)") (class "Default")
      (node (ref "MD1") (pin "32") (pinfunction "NC_32") (pintype "passive+no_connect"))
    )
    (net (code "47") (name "unconnected-(MD1-NC-Pad33)") (class "Default")
      (node (ref "MD1") (pin "33") (pinfunction "NC_33") (pintype "passive+no_connect"))
    )
    (net (code "48") (name "unconnected-(MD1-NC-Pad34)") (class "Default")
      (node (ref "MD1") (pin "34") (pinfunction "NC_34") (pintype "passive+no_connect"))
    )
    (net (code "49") (name "unconnected-(MD1-NC-Pad35)") (class "Default")
      (node (ref "MD1") (pin "35") (pinfunction "NC_35") (pintype "passive+no_connect"))
    )
    (net (code "50") (name "unconnected-(MD1-RXD0-Pad30)") (class "Default")
      (node (ref "MD1") (pin "30") (pinfunction "RXD0_30") (pintype "bidirectional"))
    )
    (net (code "51") (name "unconnected-(MD1-TXD0-Pad31)") (class "Default")
      (node (ref "MD1") (pin "31") (pinfunction "TXD0_31") (pintype "bidirectional"))
    )
    (net (code "52") (name "unconnected-(SW1-A-Pad1)") (class "Default")
      (node (ref "SW1") (pin "1") (pinfunction "A_1") (pintype "passive+no_connect"))
    )
    (net (code "53") (name "unconnected-(SW1-B-Pad3)") (class "Default")
      (node (ref "SW1") (pin "3") (pinfunction "B_3") (pintype "passive+no_connect"))
    )
    (net (code "54") (name "unconnected-(SW2-A-Pad2)") (class "Default")
      (node (ref "SW2") (pin "2") (pinfunction "A_2") (pintype "passive+no_connect"))
    )
    (net (code "55") (name "unconnected-(SW2-B-Pad4)") (class "Default")
      (node (ref "SW2") (pin "4") (pinfunction "B_4") (pintype "passive+no_connect"))
    )
    (net (code "56") (name "unconnected-(SW3-A-Pad2)") (class "Default")
      (node (ref "SW3") (pin "2") (pinfunction "A_2") (pintype "passive+no_connect"))
    )
    (net (code "57") (name "unconnected-(SW3-B-Pad4)") (class "Default")
      (node (ref "SW3") (pin "4") (pinfunction "B_4") (pintype "passive+no_connect"))
    )
    (net (code "58") (name "unconnected-(SW4-COM-1-Pad2)") (class "Default")
      (node (ref "SW4") (pin "2") (pinfunction "COM-1_2") (pintype "power_in+no_connect"))
    )
    (net (code "59") (name "unconnected-(SW4-NC-1-Pad3)") (class "Default")
      (node (ref "SW4") (pin "3") (pinfunction "NC-1_3") (pintype "bidirectional+no_connect"))
    )
    (net (code "60") (name "unconnected-(SW4-NC-2-Pad6)") (class "Default")
      (node (ref "SW4") (pin "6") (pinfunction "NC-2_6") (pintype "bidirectional+no_connect"))
    )
    (net (code "61") (name "unconnected-(SW4-NO-1-Pad1)") (class "Default")
      (node (ref "SW4") (pin "1") (pinfunction "NO-1_1") (pintype "bidirectional+no_connect"))
    )
    (net (code "62") (name "unconnected-(U2-NC-Pad1)") (class "Default")
      (node (ref "U2") (pin "1") (pinfunction "NC_1") (pintype "passive+no_connect"))
    )
    (net (code "63") (name "unconnected-(U2-NC-Pad2)") (class "Default")
      (node (ref "U2") (pin "2") (pinfunction "NC_2") (pintype "passive+no_connect"))
    )
    (net (code "64") (name "unconnected-(U2-NC-Pad3)") (class "Default")
      (node (ref "U2") (pin "3") (pinfunction "NC_3") (pintype "passive+no_connect"))
    )
    (net (code "65") (name "unconnected-(U2-NC-Pad4)") (class "Default")
      (node (ref "U2") (pin "4") (pinfunction "NC_4") (pintype "passive+no_connect"))
    )
    (net (code "66") (name "unconnected-(U2-NC-Pad5)") (class "Default")
      (node (ref "U2") (pin "5") (pinfunction "NC_5") (pintype "passive+no_connect"))
    )
    (net (code "67") (name "unconnected-(U2-NC-Pad8)") (class "Default")
      (node (ref "U2") (pin "8") (pinfunction "NC_8") (pintype "passive+no_connect"))
    )
    (net (code "68") (name "unconnected-(U2-NC-Pad11)") (class "Default")
      (node (ref "U2") (pin "11") (pinfunction "NC_11") (pintype "passive+no_connect"))
    )
    (net (code "69") (name "unconnected-(U2-NC-Pad12)") (class "Default")
      (node (ref "U2") (pin "12") (pinfunction "NC_12") (pintype "passive+no_connect"))
    )
    (net (code "70") (name "unconnected-(U2-NC-Pad13)") (class "Default")
      (node (ref "U2") (pin "13") (pinfunction "NC_13") (pintype "passive+no_connect"))
    )
    (net (code "71") (name "unconnected-(U2-NC-Pad14)") (class "Default")
      (node (ref "U2") (pin "14") (pinfunction "NC_14") (pintype "passive+no_connect"))
    )
    (net (code "72") (name "unconnected-(U2-NC-Pad15)") (class "Default")
      (node (ref "U2") (pin "15") (pinfunction "NC_15") (pintype "passive+no_connect"))
    )
    (net (code "73") (name "unconnected-(U2-NC-Pad16)") (class "Default")
      (node (ref "U2") (pin "16") (pinfunction "NC_16") (pintype "passive+no_connect"))
    )
    (net (code "74") (name "unconnected-(U2-NC-Pad17)") (class "Default")
      (node (ref "U2") (pin "17") (pinfunction "NC_17") (pintype "passive+no_connect"))
    )
    (net (code "75") (name "unconnected-(U2-NC-Pad18)") (class "Default")
      (node (ref "U2") (pin "18") (pinfunction "NC_18") (pintype "passive+no_connect"))
    )
    (net (code "76") (name "unconnected-(U4-NC-Pad1)") (class "Default")
      (node (ref "U4") (pin "1") (pinfunction "NC_1") (pintype "passive+no_connect"))
    )
  )
)
